# HL_sensors_pcb_all.net
KiCad netlist of a schematic drawn in EAGLE
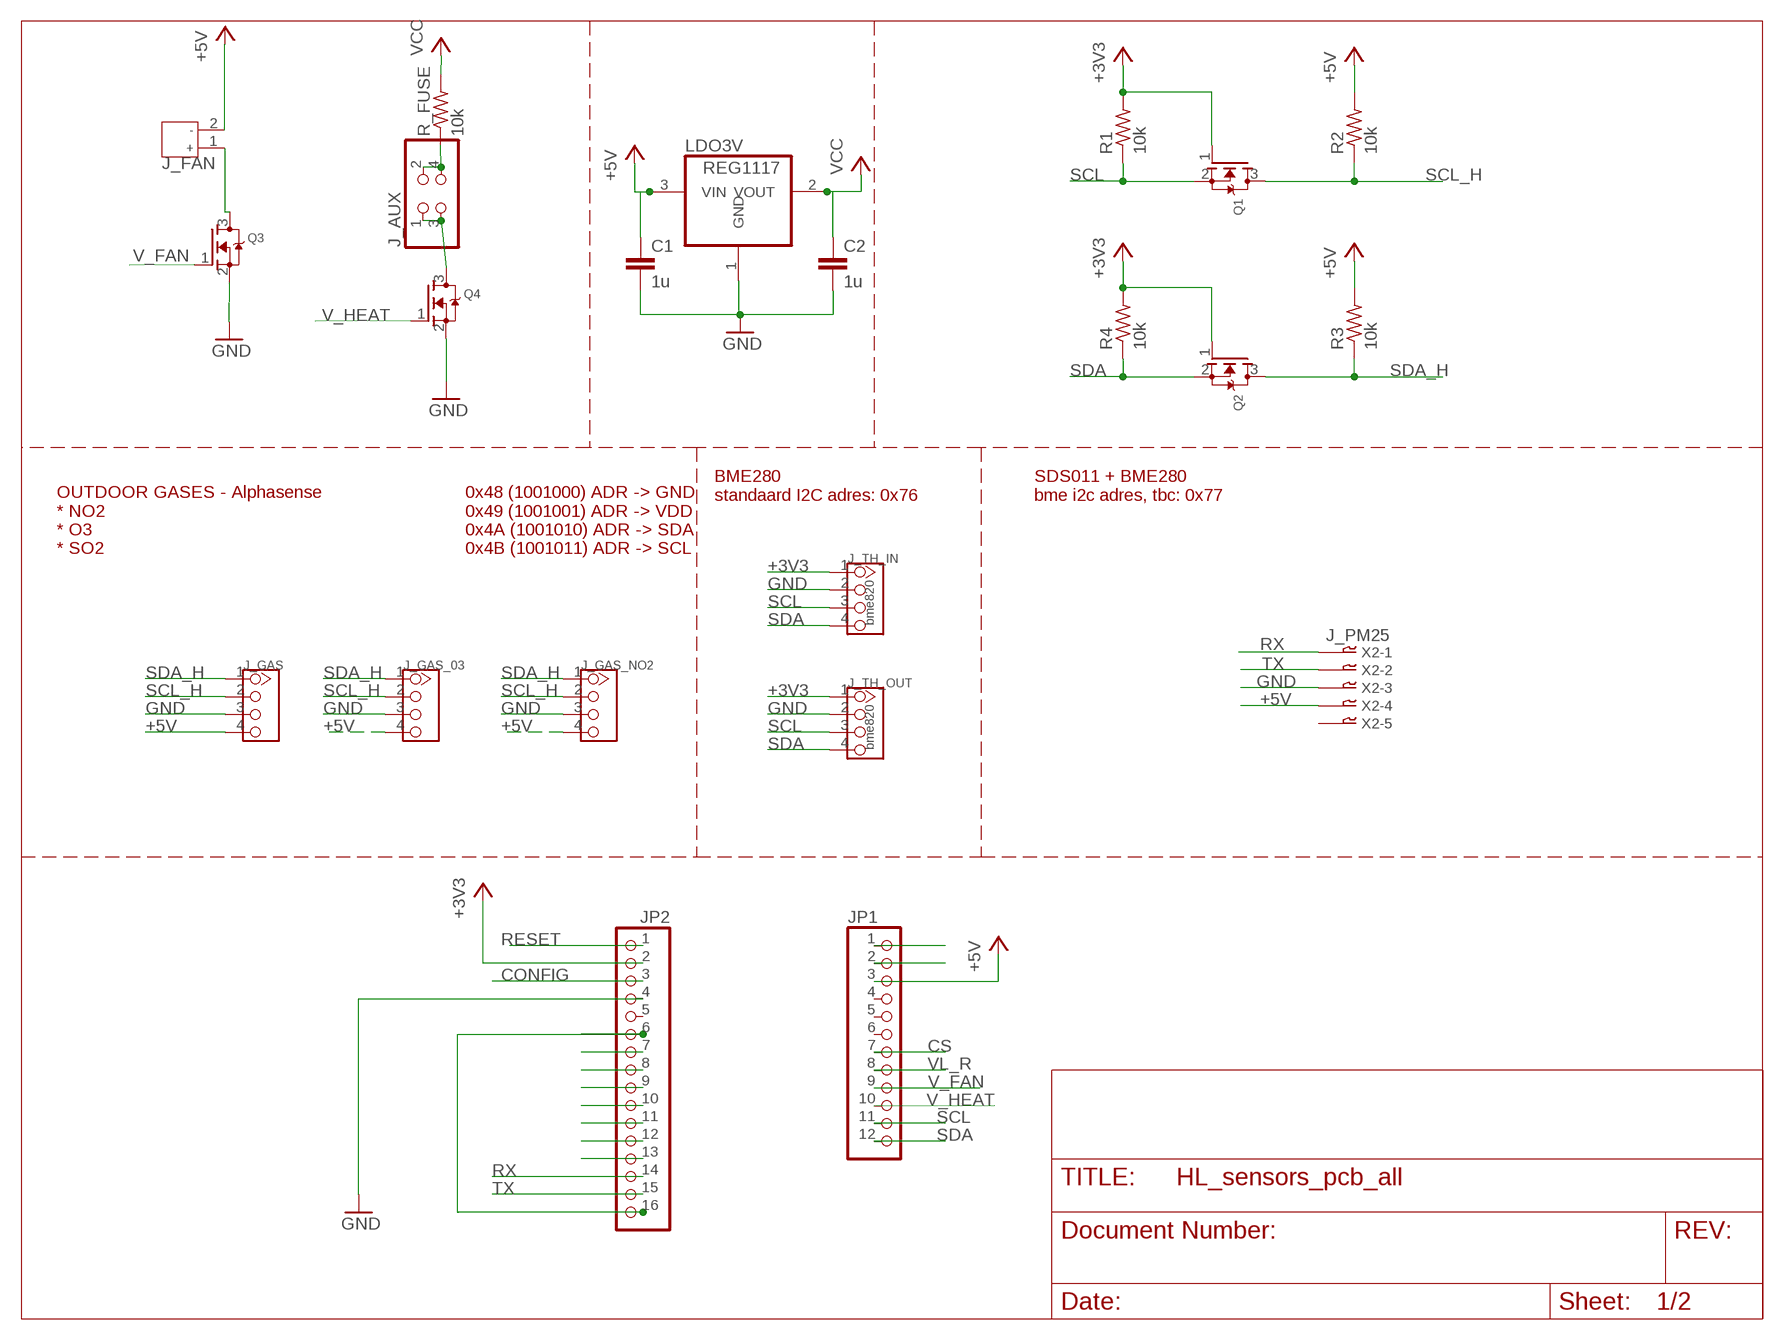
[diagram p0: schematic, sheet 1]

(export (version "E")
  (design (tool "Eeschema 10.0.6"))
  (components
    (comp (ref "C1")
      (value "1u")
      (footprint "eagle-import:C1206K")
      (libsource (lib "eagle-import") (part "C-EUC1206K"))
    )
    (comp (ref "C2")
      (value "1u")
      (footprint "eagle-import:C1206K")
      (libsource (lib "eagle-import") (part "C-EUC1206K"))
    )
    (comp (ref "JP1")
      (value "HEADER-1X12OVAL")
      (footprint "eagle-import:1X12_OVAL")
      (libsource (lib "eagle-import") (part "HEADER-1X12OVAL"))
    )
    (comp (ref "JP2")
      (value "HEADER-1X16")
      (footprint "eagle-import:1X16_OVAL")
      (libsource (lib "eagle-import") (part "HEADER-1X16"))
    )
    (comp (ref "J_AUX")
      (value "PINHD-2X2")
      (footprint "eagle-import:2X02")
      (libsource (lib "eagle-import") (part "PINHD-2X2"))
    )
    (comp (ref "J_FAN")
      (value "JACK-JST-2P-PW'2.0'")
      (footprint "eagle-import:JST-2.0")
      (libsource (lib "eagle-import") (part "JACK-JST-2P-PW'2.0'"))
    )
    (comp (ref "J_GAS")
      (value "TWIG-4P-2.0-2.0")
      (footprint "eagle-import:4P-2.0")
      (libsource (lib "eagle-import") (part "TWIG-4P-2.0-2.0"))
    )
    (comp (ref "J_GAS_03")
      (value "TWIG-4P-2.0-2.0")
      (footprint "eagle-import:4P-2.0")
      (libsource (lib "eagle-import") (part "TWIG-4P-2.0-2.0"))
    )
    (comp (ref "J_GAS_NO2")
      (value "TWIG-4P-2.0-2.0")
      (footprint "eagle-import:4P-2.0")
      (libsource (lib "eagle-import") (part "TWIG-4P-2.0-2.0"))
    )
    (comp (ref "J_TH_IN")
      (value "bme820")
      (footprint "eagle-import:4P-2.0")
      (libsource (lib "eagle-import") (part "TWIG-4P-2.0-2.0"))
    )
    (comp (ref "J_TH_OUT")
      (value "bme820")
      (footprint "eagle-import:4P-2.0")
      (libsource (lib "eagle-import") (part "TWIG-4P-2.0-2.0"))
    )
    (comp (ref "LDO3V")
      (value "REG1117")
      (footprint "eagle-import:SOT223")
      (libsource (lib "eagle-import") (part "REG1117"))
    )
    (comp (ref "Q1")
      (value "MOSFET-NWIDE")
      (footprint "eagle-import:SOT23-WIDE")
      (libsource (lib "eagle-import") (part "MOSFET-NWIDE"))
    )
    (comp (ref "Q2")
      (value "MOSFET-NWIDE")
      (footprint "eagle-import:SOT23-WIDE")
      (libsource (lib "eagle-import") (part "MOSFET-NWIDE"))
    )
    (comp (ref "Q3")
      (value "MOSFET-NWIDE")
      (footprint "eagle-import:SOT23-WIDE")
      (libsource (lib "eagle-import") (part "MOSFET-NWIDE"))
    )
    (comp (ref "Q4")
      (value "MOSFET-NWIDE")
      (footprint "eagle-import:SOT23-WIDE")
      (libsource (lib "eagle-import") (part "MOSFET-NWIDE"))
    )
    (comp (ref "R1")
      (value "10k")
      (footprint "eagle-import:1206")
      (libsource (lib "eagle-import") (part "RESISTOR1206"))
    )
    (comp (ref "R2")
      (value "10k")
      (footprint "eagle-import:1206")
      (libsource (lib "eagle-import") (part "RESISTOR1206"))
    )
    (comp (ref "R3")
      (value "10k")
      (footprint "eagle-import:1206")
      (libsource (lib "eagle-import") (part "RESISTOR1206"))
    )
    (comp (ref "R4")
      (value "10k")
      (footprint "eagle-import:1206")
      (libsource (lib "eagle-import") (part "RESISTOR1206"))
    )
    (comp (ref "R_FUSE")
      (value "10k")
      (footprint "eagle-import:1206")
      (libsource (lib "eagle-import") (part "RESISTOR1206"))
    )
    (comp (ref "X2")
      (value "J_PM25")
      (footprint "eagle-import:B5B-XH")
      (libsource (lib "eagle-import") (part "05-JST-B5B-XH-A"))
    )
  )
  (nets
    (net (code "1") (name "+3V3") (class "Default")
      (node (ref "JP2") (pin "2") (pinfunction "2_2") (pintype "passive"))
      (node (ref "J_TH_IN") (pin "1") (pinfunction "1_1") (pintype "bidirectional"))
      (node (ref "J_TH_OUT") (pin "1") (pinfunction "1_1") (pintype "bidirectional"))
      (node (ref "Q1") (pin "1") (pinfunction "G_1") (pintype "bidirectional"))
      (node (ref "Q2") (pin "1") (pinfunction "G_1") (pintype "bidirectional"))
      (node (ref "R1") (pin "2") (pinfunction "2_2") (pintype "passive"))
      (node (ref "R4") (pin "2") (pinfunction "2_2") (pintype "passive"))
    )
    (net (code "2") (name "+5V") (class "Default")
      (node (ref "C1") (pin "1") (pinfunction "1_1") (pintype "passive"))
      (node (ref "JP1") (pin "3") (pinfunction "3_3") (pintype "passive"))
      (node (ref "J_FAN") (pin "2") (pinfunction "P$2_2") (pintype "bidirectional"))
      (node (ref "J_GAS") (pin "4") (pinfunction "4_4") (pintype "bidirectional"))
      (node (ref "J_GAS_03") (pin "4") (pinfunction "4_4") (pintype "bidirectional"))
      (node (ref "J_GAS_NO2") (pin "4") (pinfunction "4_4") (pintype "bidirectional"))
      (node (ref "LDO3V") (pin "3") (pinfunction "VIN_3") (pintype "input"))
      (node (ref "R2") (pin "2") (pinfunction "2_2") (pintype "passive"))
      (node (ref "R3") (pin "2") (pinfunction "2_2") (pintype "passive"))
      (node (ref "X2") (pin "P$4") (pinfunction "1_P$4") (pintype "passive"))
    )
    (net (code "3") (name "CONFIG") (class "Default")
      (node (ref "JP2") (pin "3") (pinfunction "3_3") (pintype "passive"))
    )
    (net (code "4") (name "CS") (class "Default")
      (node (ref "JP1") (pin "7") (pinfunction "7_7") (pintype "passive"))
    )
    (net (code "5") (name "GND") (class "Default")
      (node (ref "C1") (pin "2") (pinfunction "2_2") (pintype "passive"))
      (node (ref "C2") (pin "2") (pinfunction "2_2") (pintype "passive"))
      (node (ref "JP2") (pin "4") (pinfunction "4_4") (pintype "passive"))
      (node (ref "J_GAS") (pin "3") (pinfunction "3_3") (pintype "bidirectional"))
      (node (ref "J_GAS_03") (pin "3") (pinfunction "3_3") (pintype "bidirectional"))
      (node (ref "J_GAS_NO2") (pin "3") (pinfunction "3_3") (pintype "bidirectional"))
      (node (ref "J_TH_IN") (pin "2") (pinfunction "2_2") (pintype "bidirectional"))
      (node (ref "J_TH_OUT") (pin "2") (pinfunction "2_2") (pintype "bidirectional"))
      (node (ref "LDO3V") (pin "1") (pinfunction "GND_1") (pintype "power_in"))
      (node (ref "Q3") (pin "2") (pinfunction "S_2") (pintype "bidirectional"))
      (node (ref "Q4") (pin "2") (pinfunction "S_2") (pintype "bidirectional"))
      (node (ref "X2") (pin "P$3") (pinfunction "1_P$3") (pintype "passive"))
    )
    (net (code "6") (name "Net-(JP2-Pad16)") (class "Default")
      (node (ref "JP2") (pin "16") (pinfunction "16_16") (pintype "passive"))
      (node (ref "JP2") (pin "6") (pinfunction "6_6") (pintype "passive"))
    )
    (net (code "7") (name "Net-(J_AUX-Pad2)") (class "Default")
      (node (ref "J_AUX") (pin "2") (pinfunction "2_2") (pintype "passive"))
      (node (ref "J_AUX") (pin "4") (pinfunction "4_4") (pintype "passive"))
      (node (ref "R_FUSE") (pin "1") (pinfunction "1_1") (pintype "passive"))
    )
    (net (code "8") (name "Net-(J_FAN-P$1)") (class "Default")
      (node (ref "J_FAN") (pin "1") (pinfunction "P$1_1") (pintype "bidirectional"))
      (node (ref "Q3") (pin "3") (pinfunction "D_3") (pintype "bidirectional"))
    )
    (net (code "9") (name "Net-(Q4-D)") (class "Default")
      (node (ref "J_AUX") (pin "1") (pinfunction "1_1") (pintype "passive"))
      (node (ref "J_AUX") (pin "3") (pinfunction "3_3") (pintype "passive"))
      (node (ref "Q4") (pin "3") (pinfunction "D_3") (pintype "bidirectional"))
    )
    (net (code "10") (name "RESET") (class "Default")
      (node (ref "JP2") (pin "1") (pinfunction "1_1") (pintype "passive"))
    )
    (net (code "11") (name "RX") (class "Default")
      (node (ref "JP2") (pin "14") (pinfunction "14_14") (pintype "passive"))
      (node (ref "X2") (pin "P$1") (pinfunction "1_P$1") (pintype "passive"))
    )
    (net (code "12") (name "SCL") (class "Default")
      (node (ref "JP1") (pin "11") (pinfunction "11_11") (pintype "passive"))
      (node (ref "J_TH_IN") (pin "3") (pinfunction "3_3") (pintype "bidirectional"))
      (node (ref "J_TH_OUT") (pin "3") (pinfunction "3_3") (pintype "bidirectional"))
      (node (ref "Q1") (pin "2") (pinfunction "S_2") (pintype "bidirectional"))
      (node (ref "R1") (pin "1") (pinfunction "1_1") (pintype "passive"))
    )
    (net (code "13") (name "SCL_H") (class "Default")
      (node (ref "J_GAS") (pin "2") (pinfunction "2_2") (pintype "bidirectional"))
      (node (ref "J_GAS_03") (pin "2") (pinfunction "2_2") (pintype "bidirectional"))
      (node (ref "J_GAS_NO2") (pin "2") (pinfunction "2_2") (pintype "bidirectional"))
      (node (ref "Q1") (pin "3") (pinfunction "D_3") (pintype "bidirectional"))
      (node (ref "R2") (pin "1") (pinfunction "1_1") (pintype "passive"))
    )
    (net (code "14") (name "SDA") (class "Default")
      (node (ref "JP1") (pin "12") (pinfunction "12_12") (pintype "passive"))
      (node (ref "J_TH_IN") (pin "4") (pinfunction "4_4") (pintype "bidirectional"))
      (node (ref "J_TH_OUT") (pin "4") (pinfunction "4_4") (pintype "bidirectional"))
      (node (ref "Q2") (pin "2") (pinfunction "S_2") (pintype "bidirectional"))
      (node (ref "R4") (pin "1") (pinfunction "1_1") (pintype "passive"))
    )
    (net (code "15") (name "SDA_H") (class "Default")
      (node (ref "J_GAS") (pin "1") (pinfunction "1_1") (pintype "bidirectional"))
      (node (ref "J_GAS_03") (pin "1") (pinfunction "1_1") (pintype "bidirectional"))
      (node (ref "J_GAS_NO2") (pin "1") (pinfunction "1_1") (pintype "bidirectional"))
      (node (ref "Q2") (pin "3") (pinfunction "D_3") (pintype "bidirectional"))
      (node (ref "R3") (pin "1") (pinfunction "1_1") (pintype "passive"))
    )
    (net (code "16") (name "TX") (class "Default")
      (node (ref "JP2") (pin "15") (pinfunction "15_15") (pintype "passive"))
      (node (ref "X2") (pin "P$2") (pinfunction "1_P$2") (pintype "passive"))
    )
    (net (code "17") (name "VCC") (class "Default")
      (node (ref "C2") (pin "1") (pinfunction "1_1") (pintype "passive"))
      (node (ref "LDO3V") (pin "2") (pinfunction "VOUT_2") (pintype "output"))
      (node (ref "R_FUSE") (pin "2") (pinfunction "2_2") (pintype "passive"))
    )
    (net (code "18") (name "VL_R") (class "Default")
      (node (ref "JP1") (pin "8") (pinfunction "8_8") (pintype "passive"))
    )
    (net (code "19") (name "V_FAN") (class "Default")
      (node (ref "JP1") (pin "9") (pinfunction "9_9") (pintype "passive"))
      (node (ref "Q3") (pin "1") (pinfunction "G_1") (pintype "bidirectional"))
    )
    (net (code "20") (name "V_HEAT") (class "Default")
      (node (ref "JP1") (pin "10") (pinfunction "10_10") (pintype "passive"))
      (node (ref "Q4") (pin "1") (pinfunction "G_1") (pintype "bidirectional"))
    )
    (net (code "21") (name "unconnected-(JP1-Pad1)") (class "Default")
      (node (ref "JP1") (pin "1") (pinfunction "1_1") (pintype "passive"))
    )
    (net (code "22") (name "unconnected-(JP1-Pad2)") (class "Default")
      (node (ref "JP1") (pin "2") (pinfunction "2_2") (pintype "passive"))
    )
    (net (code "23") (name "unconnected-(JP1-Pad4)") (class "Default")
      (node (ref "JP1") (pin "4") (pinfunction "4_4") (pintype "passive"))
    )
    (net (code "24") (name "unconnected-(JP1-Pad5)") (class "Default")
      (node (ref "JP1") (pin "5") (pinfunction "5_5") (pintype "passive"))
    )
    (net (code "25") (name "unconnected-(JP1-Pad6)") (class "Default")
      (node (ref "JP1") (pin "6") (pinfunction "6_6") (pintype "passive"))
    )
    (net (code "26") (name "unconnected-(JP2-Pad5)") (class "Default")
      (node (ref "JP2") (pin "5") (pinfunction "5_5") (pintype "passive"))
    )
    (net (code "27") (name "unconnected-(JP2-Pad7)") (class "Default")
      (node (ref "JP2") (pin "7") (pinfunction "7_7") (pintype "passive"))
    )
    (net (code "28") (name "unconnected-(JP2-Pad8)") (class "Default")
      (node (ref "JP2") (pin "8") (pinfunction "8_8") (pintype "passive"))
    )
    (net (code "29") (name "unconnected-(JP2-Pad9)") (class "Default")
      (node (ref "JP2") (pin "9") (pinfunction "9_9") (pintype "passive"))
    )
    (net (code "30") (name "unconnected-(JP2-Pad10)") (class "Default")
      (node (ref "JP2") (pin "10") (pinfunction "10_10") (pintype "passive"))
    )
    (net (code "31") (name "unconnected-(JP2-Pad11)") (class "Default")
      (node (ref "JP2") (pin "11") (pinfunction "11_11") (pintype "passive"))
    )
    (net (code "32") (name "unconnected-(JP2-Pad12)") (class "Default")
      (node (ref "JP2") (pin "12") (pinfunction "12_12") (pintype "passive"))
    )
    (net (code "33") (name "unconnected-(JP2-Pad13)") (class "Default")
      (node (ref "JP2") (pin "13") (pinfunction "13_13") (pintype "passive"))
    )
    (net (code "34") (name "unconnected-(X2E-1-PadP$5)") (class "Default")
      (node (ref "X2") (pin "P$5") (pinfunction "1_P$5") (pintype "passive"))
    )
  )
)
